# dice.net
KiCad netlist of a schematic drawn in EAGLE
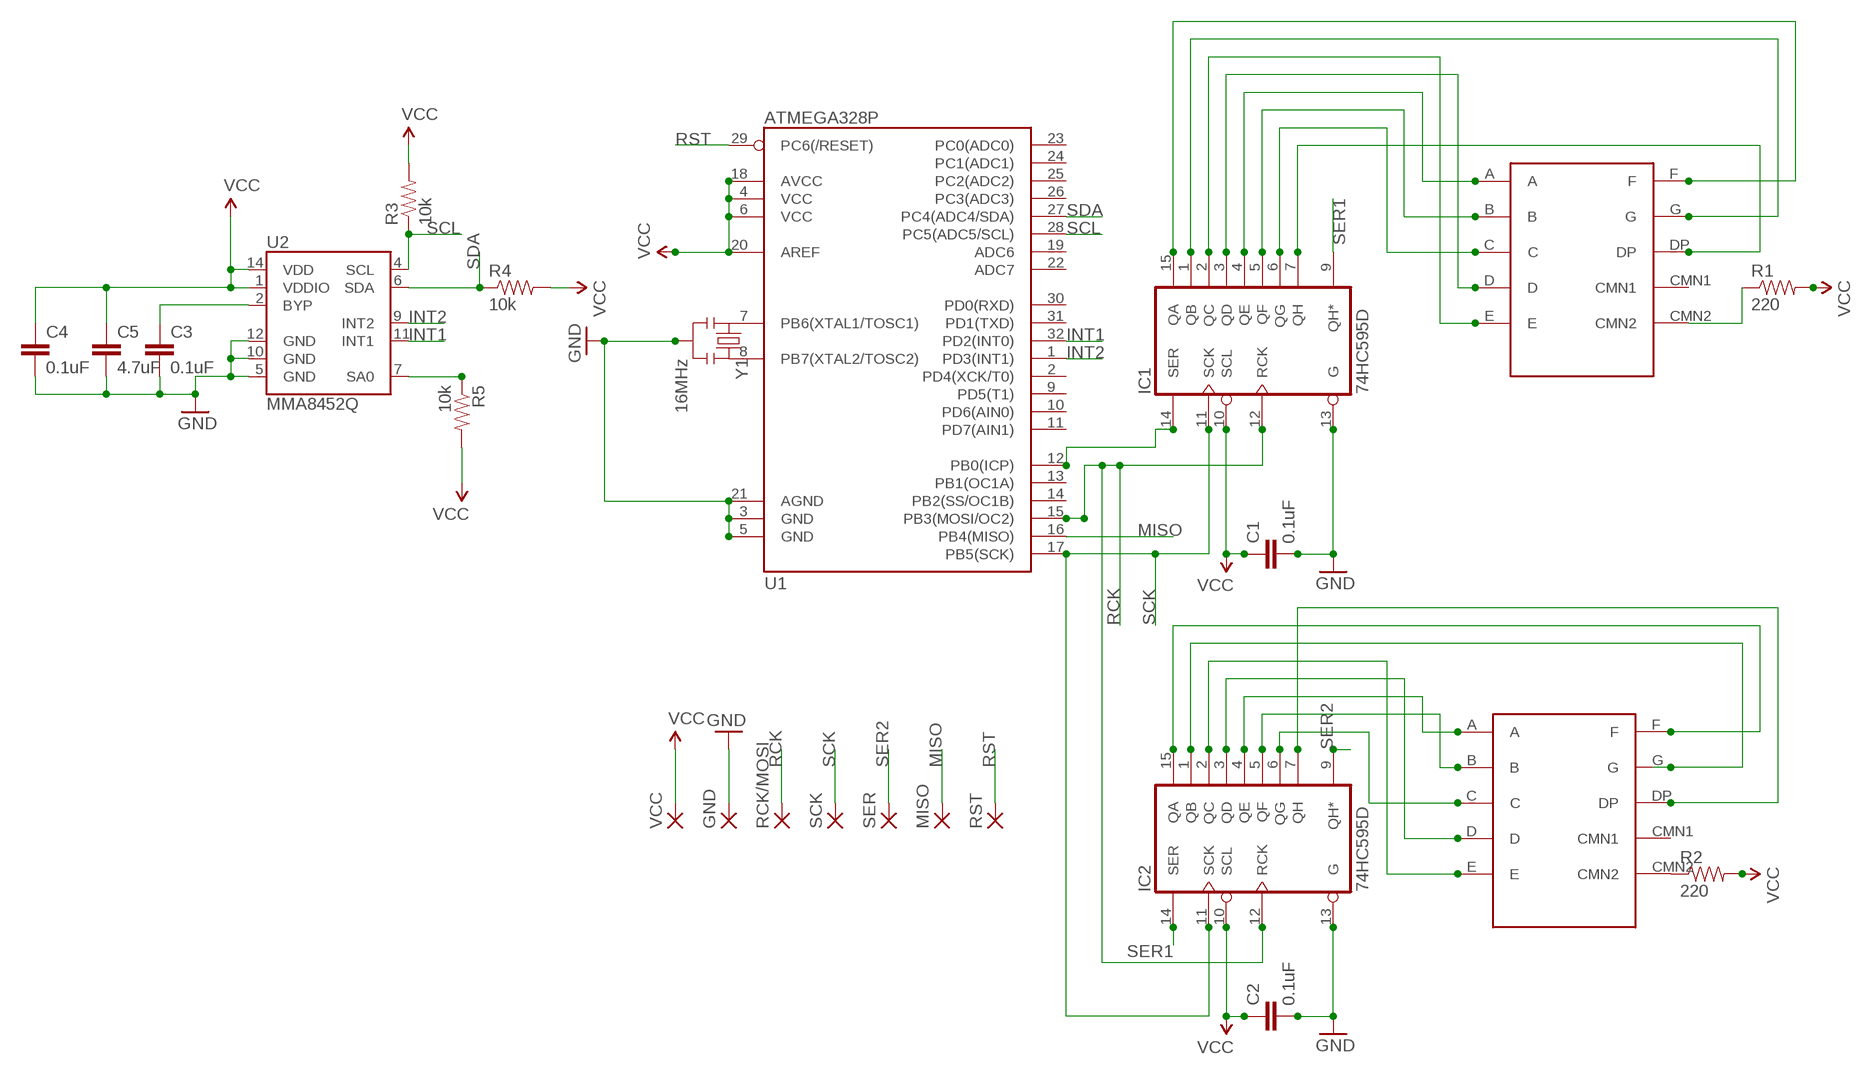
[diagram p0: schematic, sheet 1]

(export (version "E")
  (design (tool "Eeschema 10.0.6"))
  (components
    (comp (ref "C1")
      (value "0.1uF")
      (footprint "eagle-import:0402-CAP")
      (libsource (lib "eagle-import") (part ".1UF-CER"))
    )
    (comp (ref "C2")
      (value "0.1uF")
      (footprint "eagle-import:0402-CAP")
      (fields (field (name "PROD_ID") "CAP-00810"))
      (libsource (lib "eagle-import") (part ".1UF-CER"))
    )
    (comp (ref "C3")
      (value "0.1uF")
      (footprint "eagle-import:0402-CAP")
      (libsource (lib "eagle-import") (part ".1UF-CER"))
    )
    (comp (ref "C4")
      (value "0.1uF")
      (footprint "eagle-import:0402-CAP")
      (libsource (lib "eagle-import") (part ".1UF-CER"))
    )
    (comp (ref "C5")
      (value "4.7uF")
      (footprint "eagle-import:0402-CAP")
      (libsource (lib "eagle-import") (part "4.7UF-6.3V-10%(0603)"))
    )
    (comp (ref "GND")
      (value "1,6/0,8")
      (footprint "eagle-import:1,6_0,8")
      (libsource (lib "eagle-import") (part "1,6/0,8"))
    )
    (comp (ref "IC1")
      (value "74HC595D")
      (footprint "eagle-import:SO16")
      (libsource (lib "eagle-import") (part "74595DHC"))
    )
    (comp (ref "IC2")
      (value "74HC595D")
      (footprint "eagle-import:SO16")
      (libsource (lib "eagle-import") (part "74595DHC"))
    )
    (comp (ref "MISO")
      (value "1,6/0,8")
      (footprint "eagle-import:1,6_0,8")
      (libsource (lib "eagle-import") (part "1,6/0,8"))
    )
    (comp (ref "R1")
      (value "220")
      (footprint "eagle-import:0603-RES")
      (libsource (lib "eagle-import") (part "220-5%"))
    )
    (comp (ref "R2")
      (value "220")
      (footprint "eagle-import:0603-RES")
      (fields (field (name "PROD_ID") "RES-07866"))
      (libsource (lib "eagle-import") (part "220-5%"))
    )
    (comp (ref "R3")
      (value "10k")
      (footprint "eagle-import:0402-RES")
      (libsource (lib "eagle-import") (part "RESISTOR0402-RES"))
    )
    (comp (ref "R4")
      (value "10k")
      (footprint "eagle-import:0402-RES")
      (libsource (lib "eagle-import") (part "RESISTOR0402-RES"))
    )
    (comp (ref "R5")
      (value "10k")
      (footprint "eagle-import:0402-RES")
      (libsource (lib "eagle-import") (part "RESISTOR0402-RES"))
    )
    (comp (ref "RCK/MOSI")
      (value "1,6/0,8")
      (footprint "eagle-import:1,6_0,8")
      (libsource (lib "eagle-import") (part "1,6/0,8"))
    )
    (comp (ref "RST")
      (value "1,6/0,8")
      (footprint "eagle-import:1,6_0,8")
      (libsource (lib "eagle-import") (part "1,6/0,8"))
    )
    (comp (ref "SCK")
      (value "1,6/0,8")
      (footprint "eagle-import:1,6_0,8")
      (libsource (lib "eagle-import") (part "1,6/0,8"))
    )
    (comp (ref "SER")
      (value "1,6/0,8")
      (footprint "eagle-import:1,6_0,8")
      (libsource (lib "eagle-import") (part "1,6/0,8"))
    )
    (comp (ref "U$1")
      (value "LUMEXSMHTA5604RISIT")
      (footprint "eagle-import:7SEG-10SMD")
      (libsource (lib "eagle-import") (part "LUMEXSMHTA5604RISIT"))
    )
    (comp (ref "U$2")
      (value "LUMEXSMHTA5604RISIT")
      (footprint "eagle-import:7SEG-10SMD")
      (libsource (lib "eagle-import") (part "LUMEXSMHTA5604RISIT"))
    )
    (comp (ref "U1")
      (value "ATMEGA328P")
      (footprint "eagle-import:TQFP32-08")
      (libsource (lib "eagle-import") (part "ATMEGA328_SMT"))
    )
    (comp (ref "U2")
      (value "MMA8452Q")
      (footprint "eagle-import:QFN-16_0.5MM")
      (libsource (lib "eagle-import") (part "MMA8452Q"))
    )
    (comp (ref "VCC")
      (value "1,6/0,8")
      (footprint "eagle-import:1,6_0,8")
      (libsource (lib "eagle-import") (part "1,6/0,8"))
    )
    (comp (ref "Y1")
      (value "16MHz")
      (footprint "eagle-import:RESONATOR-SMD")
      (libsource (lib "eagle-import") (part "RESONATOR16MHZ"))
    )
  )
  (nets
    (net (code "1") (name "/INT1") (class "Default")
      (node (ref "U1") (pin "32") (pinfunction "PD2(INT0)_32") (pintype "bidirectional"))
      (node (ref "U2") (pin "11") (pinfunction "INT1_11") (pintype "bidirectional"))
    )
    (net (code "2") (name "/INT2") (class "Default")
      (node (ref "U1") (pin "1") (pinfunction "PD3(INT1)_1") (pintype "bidirectional"))
      (node (ref "U2") (pin "9") (pinfunction "INT2_9") (pintype "bidirectional"))
    )
    (net (code "3") (name "/MISO") (class "Default")
      (node (ref "MISO") (pin "1") (pinfunction "P_1") (pintype "passive"))
      (node (ref "U1") (pin "16") (pinfunction "PB4(MISO)_16") (pintype "bidirectional"))
    )
    (net (code "4") (name "/RCK") (class "Default")
      (node (ref "IC1") (pin "12") (pinfunction "RCK_12") (pintype "input"))
      (node (ref "IC2") (pin "12") (pinfunction "RCK_12") (pintype "input"))
      (node (ref "RCK/MOSI") (pin "1") (pinfunction "P_1") (pintype "passive"))
      (node (ref "U1") (pin "15") (pinfunction "PB3(MOSI/OC2)_15") (pintype "bidirectional"))
    )
    (net (code "5") (name "/RST") (class "Default")
      (node (ref "RST") (pin "1") (pinfunction "P_1") (pintype "passive"))
      (node (ref "U1") (pin "29") (pinfunction "PC6(/RESET)_29") (pintype "bidirectional"))
    )
    (net (code "6") (name "/SCK") (class "Default")
      (node (ref "IC1") (pin "11") (pinfunction "SCK_11") (pintype "input"))
      (node (ref "IC2") (pin "11") (pinfunction "SCK_11") (pintype "input"))
      (node (ref "SCK") (pin "1") (pinfunction "P_1") (pintype "passive"))
      (node (ref "U1") (pin "17") (pinfunction "PB5(SCK)_17") (pintype "bidirectional"))
    )
    (net (code "7") (name "/SCL") (class "Default")
      (node (ref "R3") (pin "1") (pinfunction "1_1") (pintype "passive"))
      (node (ref "U1") (pin "28") (pinfunction "PC5(ADC5/SCL)_28") (pintype "bidirectional"))
      (node (ref "U2") (pin "4") (pinfunction "SCL_4") (pintype "bidirectional"))
    )
    (net (code "8") (name "/SDA") (class "Default")
      (node (ref "R4") (pin "1") (pinfunction "1_1") (pintype "passive"))
      (node (ref "U1") (pin "27") (pinfunction "PC4(ADC4/SDA)_27") (pintype "bidirectional"))
      (node (ref "U2") (pin "6") (pinfunction "SDA_6") (pintype "bidirectional"))
    )
    (net (code "9") (name "/SER1") (class "Default")
      (node (ref "IC1") (pin "9") (pinfunction "QH*_9") (pintype "tri_state"))
      (node (ref "IC2") (pin "14") (pinfunction "SER_14") (pintype "input"))
    )
    (net (code "10") (name "/SER2") (class "Default")
      (node (ref "IC2") (pin "9") (pinfunction "QH*_9") (pintype "tri_state"))
      (node (ref "SER") (pin "1") (pinfunction "P_1") (pintype "passive"))
    )
    (net (code "11") (name "GND") (class "Default")
      (node (ref "C1") (pin "2") (pinfunction "2_2") (pintype "passive"))
      (node (ref "C2") (pin "2") (pinfunction "2_2") (pintype "passive"))
      (node (ref "C3") (pin "2") (pinfunction "2_2") (pintype "passive"))
      (node (ref "C4") (pin "2") (pinfunction "2_2") (pintype "passive"))
      (node (ref "C5") (pin "2") (pinfunction "2_2") (pintype "passive"))
      (node (ref "GND") (pin "1") (pinfunction "P_1") (pintype "passive"))
      (node (ref "IC1") (pin "13") (pinfunction "G_13") (pintype "input"))
      (node (ref "IC2") (pin "13") (pinfunction "G_13") (pintype "input"))
      (node (ref "U1") (pin "21") (pinfunction "AGND_21") (pintype "bidirectional"))
      (node (ref "U1") (pin "3") (pinfunction "GND_3") (pintype "bidirectional"))
      (node (ref "U1") (pin "5") (pinfunction "GND_5") (pintype "bidirectional"))
      (node (ref "U2") (pin "10") (pinfunction "GND_10") (pintype "bidirectional"))
      (node (ref "U2") (pin "12") (pinfunction "GND_12") (pintype "bidirectional"))
      (node (ref "U2") (pin "5") (pinfunction "GND_5") (pintype "bidirectional"))
      (node (ref "Y1") (pin "2") (pinfunction "2_2") (pintype "passive"))
    )
    (net (code "12") (name "Net-(IC1A-QA)") (class "Default")
      (node (ref "IC1") (pin "15") (pinfunction "QA_15") (pintype "tri_state"))
      (node (ref "U$1") (pin "F") (pinfunction "F_F") (pintype "bidirectional"))
    )
    (net (code "13") (name "Net-(IC1A-QB)") (class "Default")
      (node (ref "IC1") (pin "1") (pinfunction "QB_1") (pintype "tri_state"))
      (node (ref "U$1") (pin "G") (pinfunction "G_G") (pintype "bidirectional"))
    )
    (net (code "14") (name "Net-(IC1A-QC)") (class "Default")
      (node (ref "IC1") (pin "2") (pinfunction "QC_2") (pintype "tri_state"))
      (node (ref "U$1") (pin "E") (pinfunction "E_E") (pintype "bidirectional"))
    )
    (net (code "15") (name "Net-(IC1A-QD)") (class "Default")
      (node (ref "IC1") (pin "3") (pinfunction "QD_3") (pintype "tri_state"))
      (node (ref "U$1") (pin "D") (pinfunction "D_D") (pintype "bidirectional"))
    )
    (net (code "16") (name "Net-(IC1A-QE)") (class "Default")
      (node (ref "IC1") (pin "4") (pinfunction "QE_4") (pintype "tri_state"))
      (node (ref "U$1") (pin "A") (pinfunction "A_A") (pintype "bidirectional"))
    )
    (net (code "17") (name "Net-(IC1A-QF)") (class "Default")
      (node (ref "IC1") (pin "5") (pinfunction "QF_5") (pintype "tri_state"))
      (node (ref "U$1") (pin "B") (pinfunction "B_B") (pintype "bidirectional"))
    )
    (net (code "18") (name "Net-(IC1A-QG)") (class "Default")
      (node (ref "IC1") (pin "6") (pinfunction "QG_6") (pintype "tri_state"))
      (node (ref "U$1") (pin "C") (pinfunction "C_C") (pintype "bidirectional"))
    )
    (net (code "19") (name "Net-(IC1A-QH)") (class "Default")
      (node (ref "IC1") (pin "7") (pinfunction "QH_7") (pintype "tri_state"))
      (node (ref "U$1") (pin "DP") (pinfunction "DP_DP") (pintype "bidirectional"))
    )
    (net (code "20") (name "Net-(IC1A-SER)") (class "Default")
      (node (ref "IC1") (pin "14") (pinfunction "SER_14") (pintype "input"))
      (node (ref "U1") (pin "12") (pinfunction "PB0(ICP)_12") (pintype "bidirectional"))
    )
    (net (code "21") (name "Net-(IC2A-QA)") (class "Default")
      (node (ref "IC2") (pin "15") (pinfunction "QA_15") (pintype "tri_state"))
      (node (ref "U$2") (pin "F") (pinfunction "F_F") (pintype "bidirectional"))
    )
    (net (code "22") (name "Net-(IC2A-QB)") (class "Default")
      (node (ref "IC2") (pin "1") (pinfunction "QB_1") (pintype "tri_state"))
      (node (ref "U$2") (pin "G") (pinfunction "G_G") (pintype "bidirectional"))
    )
    (net (code "23") (name "Net-(IC2A-QC)") (class "Default")
      (node (ref "IC2") (pin "2") (pinfunction "QC_2") (pintype "tri_state"))
      (node (ref "U$2") (pin "E") (pinfunction "E_E") (pintype "bidirectional"))
    )
    (net (code "24") (name "Net-(IC2A-QD)") (class "Default")
      (node (ref "IC2") (pin "3") (pinfunction "QD_3") (pintype "tri_state"))
      (node (ref "U$2") (pin "D") (pinfunction "D_D") (pintype "bidirectional"))
    )
    (net (code "25") (name "Net-(IC2A-QE)") (class "Default")
      (node (ref "IC2") (pin "4") (pinfunction "QE_4") (pintype "tri_state"))
      (node (ref "U$2") (pin "A") (pinfunction "A_A") (pintype "bidirectional"))
    )
    (net (code "26") (name "Net-(IC2A-QF)") (class "Default")
      (node (ref "IC2") (pin "5") (pinfunction "QF_5") (pintype "tri_state"))
      (node (ref "U$2") (pin "B") (pinfunction "B_B") (pintype "bidirectional"))
    )
    (net (code "27") (name "Net-(IC2A-QG)") (class "Default")
      (node (ref "IC2") (pin "6") (pinfunction "QG_6") (pintype "tri_state"))
      (node (ref "U$2") (pin "C") (pinfunction "C_C") (pintype "bidirectional"))
    )
    (net (code "28") (name "Net-(IC2A-QH)") (class "Default")
      (node (ref "IC2") (pin "7") (pinfunction "QH_7") (pintype "tri_state"))
      (node (ref "U$2") (pin "DP") (pinfunction "DP_DP") (pintype "bidirectional"))
    )
    (net (code "29") (name "Net-(R1-Pad1)") (class "Default")
      (node (ref "R1") (pin "1") (pinfunction "1_1") (pintype "passive"))
      (node (ref "U$1") (pin "CMN2") (pinfunction "CMN2_CMN2") (pintype "bidirectional"))
    )
    (net (code "30") (name "Net-(R2-Pad1)") (class "Default")
      (node (ref "R2") (pin "1") (pinfunction "1_1") (pintype "passive"))
      (node (ref "U$2") (pin "CMN2") (pinfunction "CMN2_CMN2") (pintype "bidirectional"))
    )
    (net (code "31") (name "Net-(U1-PB6(XTAL1{slash}TOSC1))") (class "Default")
      (node (ref "U1") (pin "7") (pinfunction "PB6(XTAL1/TOSC1)_7") (pintype "bidirectional"))
      (node (ref "Y1") (pin "1") (pinfunction "1_1") (pintype "passive"))
    )
    (net (code "32") (name "Net-(U1-PB7(XTAL2{slash}TOSC2))") (class "Default")
      (node (ref "U1") (pin "8") (pinfunction "PB7(XTAL2/TOSC2)_8") (pintype "bidirectional"))
      (node (ref "Y1") (pin "3") (pinfunction "3_3") (pintype "passive"))
    )
    (net (code "33") (name "Net-(U2-BYP)") (class "Default")
      (node (ref "C3") (pin "1") (pinfunction "1_1") (pintype "passive"))
      (node (ref "U2") (pin "2") (pinfunction "BYP_2") (pintype "bidirectional"))
    )
    (net (code "34") (name "Net-(U2-SA0)") (class "Default")
      (node (ref "R5") (pin "1") (pinfunction "1_1") (pintype "passive"))
      (node (ref "U2") (pin "7") (pinfunction "SA0_7") (pintype "bidirectional"))
    )
    (net (code "35") (name "VCC") (class "Default")
      (node (ref "C1") (pin "1") (pinfunction "1_1") (pintype "passive"))
      (node (ref "C2") (pin "1") (pinfunction "1_1") (pintype "passive"))
      (node (ref "C4") (pin "1") (pinfunction "1_1") (pintype "passive"))
      (node (ref "C5") (pin "1") (pinfunction "1_1") (pintype "passive"))
      (node (ref "IC1") (pin "10") (pinfunction "SCL_10") (pintype "input"))
      (node (ref "IC2") (pin "10") (pinfunction "SCL_10") (pintype "input"))
      (node (ref "R1") (pin "2") (pinfunction "2_2") (pintype "passive"))
      (node (ref "R2") (pin "2") (pinfunction "2_2") (pintype "passive"))
      (node (ref "R3") (pin "2") (pinfunction "2_2") (pintype "passive"))
      (node (ref "R4") (pin "2") (pinfunction "2_2") (pintype "passive"))
      (node (ref "R5") (pin "2") (pinfunction "2_2") (pintype "passive"))
      (node (ref "U1") (pin "18") (pinfunction "AVCC_18") (pintype "bidirectional"))
      (node (ref "U1") (pin "20") (pinfunction "AREF_20") (pintype "bidirectional"))
      (node (ref "U1") (pin "4") (pinfunction "VCC_4") (pintype "bidirectional"))
      (node (ref "U1") (pin "6") (pinfunction "VCC_6") (pintype "bidirectional"))
      (node (ref "U2") (pin "1") (pinfunction "VDDIO_1") (pintype "bidirectional"))
      (node (ref "U2") (pin "14") (pinfunction "VDD_14") (pintype "bidirectional"))
      (node (ref "VCC") (pin "1") (pinfunction "P_1") (pintype "passive"))
    )
    (net (code "36") (name "unconnected-(U$1-PadCMN1)") (class "Default")
      (node (ref "U$1") (pin "CMN1") (pinfunction "CMN1_CMN1") (pintype "bidirectional"))
    )
    (net (code "37") (name "unconnected-(U$2-PadCMN1)") (class "Default")
      (node (ref "U$2") (pin "CMN1") (pinfunction "CMN1_CMN1") (pintype "bidirectional"))
    )
    (net (code "38") (name "unconnected-(U1-ADC6-Pad19)") (class "Default")
      (node (ref "U1") (pin "19") (pinfunction "ADC6_19") (pintype "bidirectional"))
    )
    (net (code "39") (name "unconnected-(U1-ADC7-Pad22)") (class "Default")
      (node (ref "U1") (pin "22") (pinfunction "ADC7_22") (pintype "bidirectional"))
    )
    (net (code "40") (name "unconnected-(U1-PB1(OC1A)-Pad13)") (class "Default")
      (node (ref "U1") (pin "13") (pinfunction "PB1(OC1A)_13") (pintype "bidirectional"))
    )
    (net (code "41") (name "unconnected-(U1-PB2(SS{slash}OC1B)-Pad14)") (class "Default")
      (node (ref "U1") (pin "14") (pinfunction "PB2(SS/OC1B)_14") (pintype "bidirectional"))
    )
    (net (code "42") (name "unconnected-(U1-PC0(ADC0)-Pad23)") (class "Default")
      (node (ref "U1") (pin "23") (pinfunction "PC0(ADC0)_23") (pintype "bidirectional"))
    )
    (net (code "43") (name "unconnected-(U1-PC1(ADC1)-Pad24)") (class "Default")
      (node (ref "U1") (pin "24") (pinfunction "PC1(ADC1)_24") (pintype "bidirectional"))
    )
    (net (code "44") (name "unconnected-(U1-PC2(ADC2)-Pad25)") (class "Default")
      (node (ref "U1") (pin "25") (pinfunction "PC2(ADC2)_25") (pintype "bidirectional"))
    )
    (net (code "45") (name "unconnected-(U1-PC3(ADC3)-Pad26)") (class "Default")
      (node (ref "U1") (pin "26") (pinfunction "PC3(ADC3)_26") (pintype "bidirectional"))
    )
    (net (code "46") (name "unconnected-(U1-PD0(RXD)-Pad30)") (class "Default")
      (node (ref "U1") (pin "30") (pinfunction "PD0(RXD)_30") (pintype "bidirectional"))
    )
    (net (code "47") (name "unconnected-(U1-PD1(TXD)-Pad31)") (class "Default")
      (node (ref "U1") (pin "31") (pinfunction "PD1(TXD)_31") (pintype "bidirectional"))
    )
    (net (code "48") (name "unconnected-(U1-PD4(XCK{slash}T0)-Pad2)") (class "Default")
      (node (ref "U1") (pin "2") (pinfunction "PD4(XCK/T0)_2") (pintype "bidirectional"))
    )
    (net (code "49") (name "unconnected-(U1-PD5(T1)-Pad9)") (class "Default")
      (node (ref "U1") (pin "9") (pinfunction "PD5(T1)_9") (pintype "bidirectional"))
    )
    (net (code "50") (name "unconnected-(U1-PD6(AIN0)-Pad10)") (class "Default")
      (node (ref "U1") (pin "10") (pinfunction "PD6(AIN0)_10") (pintype "bidirectional"))
    )
    (net (code "51") (name "unconnected-(U1-PD7(AIN1)-Pad11)") (class "Default")
      (node (ref "U1") (pin "11") (pinfunction "PD7(AIN1)_11") (pintype "bidirectional"))
    )
  )
)
